# stm32.net
KiCad netlist of a schematic drawn in Altium Designer
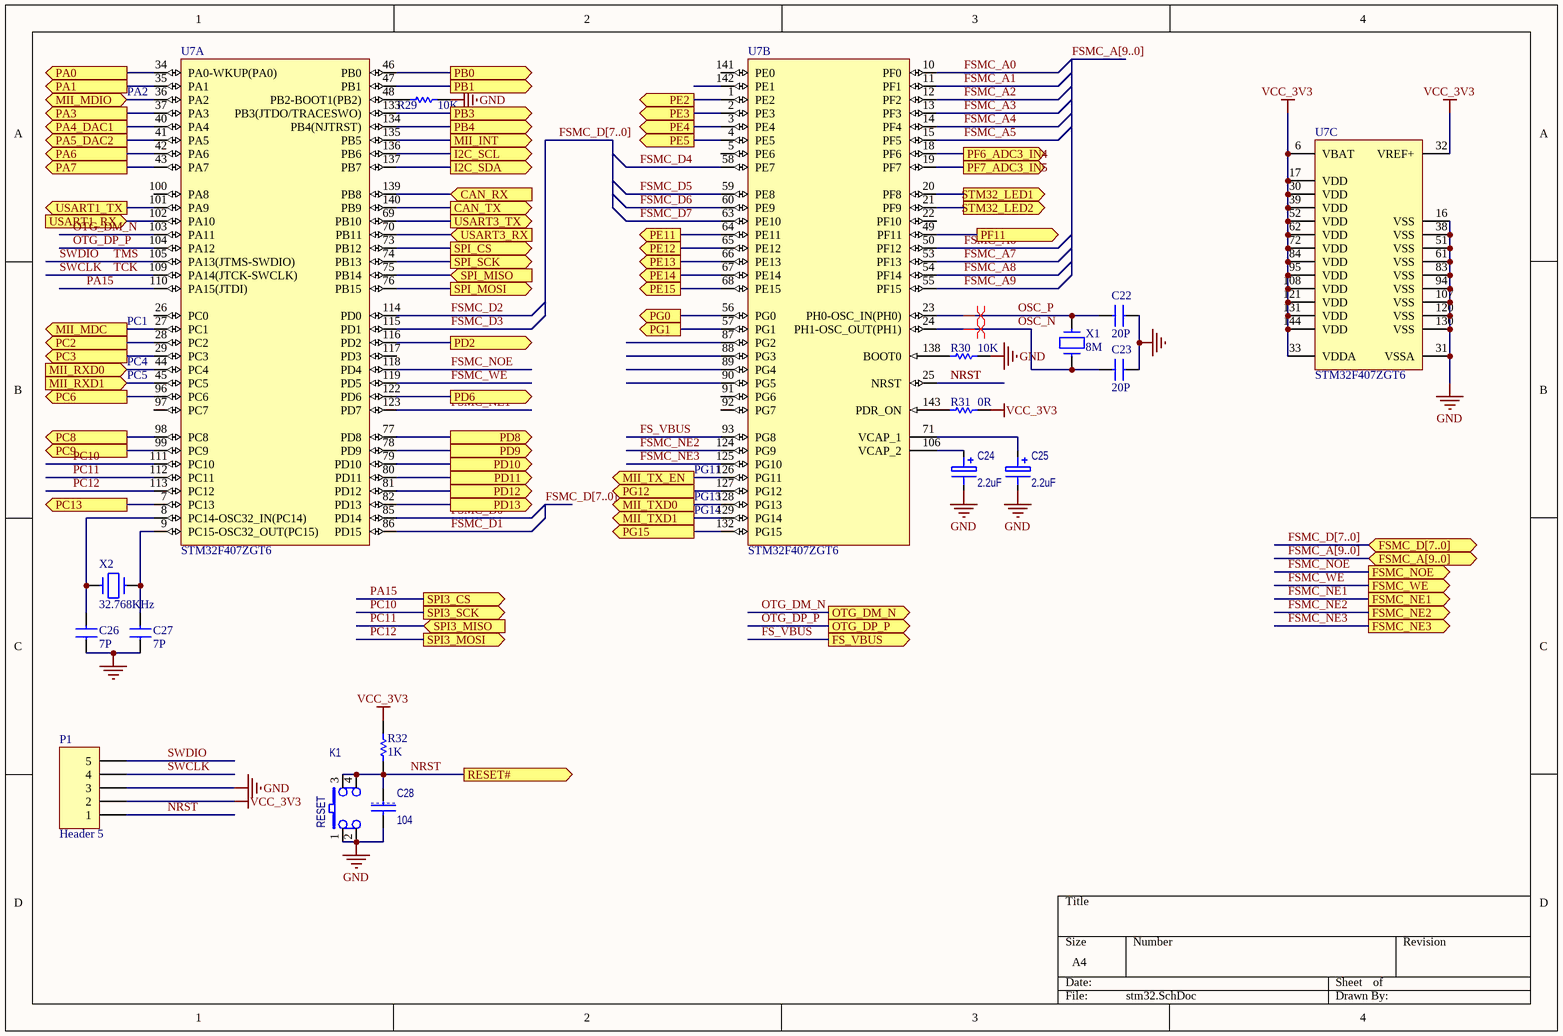
[diagram p0: stm32.SchDoc]

(export (version "E")
  (design (tool "Eeschema 10.0.6"))
  (components
    (comp (ref "C22")
      (value "20P")
      (footprint "0603C")
      (description "Capacitor")
      (libsource (lib "*") (part "CAP"))
    )
    (comp (ref "C23")
      (value "20P")
      (footprint "0603C")
      (description "Capacitor")
      (libsource (lib "*") (part "CAP"))
    )
    (comp (ref "C24") (value "2.2uF") (footprint "3216") (libsource (lib "*") (part "ELECTRO")))
    (comp (ref "C25") (value "2.2uF") (footprint "3216") (libsource (lib "*") (part "ELECTRO")))
    (comp (ref "C26")
      (value "7P")
      (footprint "0603C")
      (description "Capacitor")
      (libsource (lib "*") (part "CAP"))
    )
    (comp (ref "C27")
      (value "7P")
      (footprint "0603C")
      (description "Capacitor")
      (libsource (lib "*") (part "CAP"))
    )
    (comp (ref "C28")
      (value "104")
      (footprint "0603C")
      (description "Capacitor")
      (libsource (lib "") (part "CAP_1"))
    )
    (comp (ref "K1") (value "RESET") (footprint "SW_PIN4") (libsource (lib "*") (part "SW_PUSH2")))
    (comp (ref "P1")
      (value "Header 5")
      (footprint "HDR1X5")
      (description "Header, 5-Pin")
      (fields (field (name "PUBLISHER") "Altium Limited"))
      (libsource (lib "Miscellaneous Connectors") (part "Header 5"))
    )
    (comp (ref "R29")
      (value "10K")
      (footprint "0603R")
      (description "Semiconductor Resistor")
      (fields (field (name "PUBLISHER") "Altium Limited"))
      (libsource (lib "Miscellaneous Devices") (part "Res Semi"))
    )
    (comp (ref "R30")
      (value "10K")
      (footprint "0603R")
      (description "Semiconductor Resistor")
      (fields (field (name "PUBLISHER") "Altium Limited"))
      (libsource (lib "Miscellaneous Devices") (part "Res Semi"))
    )
    (comp (ref "R31")
      (value "0R")
      (footprint "0603R")
      (description "Semiconductor Resistor")
      (fields (field (name "Comment") "10K") (field (name "PUBLISHER") "Altium Limited"))
      (libsource (lib "Miscellaneous Devices") (part "Res Semi"))
    )
    (comp (ref "R32")
      (value "1K")
      (footprint "0603R")
      (description "Semiconductor Resistor")
      (fields (field (name "PUBLISHER") "Altium Limited"))
      (libsource (lib "Miscellaneous Devices") (part "Res Semi"))
    )
    (comp (ref "U7")
      (value "STM32F407ZGT6")
      (footprint "STM-LQFP144_N")
      (fields (field (name "MANUFACTURER") "STMicroelectronics"))
      (libsource (lib "STMicroelectronics STM32 F4") (part "STM32F407ZGT6"))
    )
    (comp (ref "X1") (value "8M") (footprint "XTAL3") (libsource (lib "*") (part "CRYSTAL")))
    (comp (ref "X2") (value "32.768KHz") (footprint "XTAL2") (libsource (lib "*") (part "CRYSTAL")))
  )
  (nets
    (net (code "1") (name "/CAN_RX") (class "Default")
      (node (ref "U7") (pin "139") (pinfunction "PB8_139") (pintype "bidirectional"))
    )
    (net (code "2") (name "/CAN_TX") (class "Default")
      (node (ref "U7") (pin "140") (pinfunction "PB9_140") (pintype "bidirectional"))
    )
    (net (code "3") (name "/FSMC_A0") (class "Default")
      (node (ref "U7") (pin "10") (pinfunction "PF0_10") (pintype "bidirectional"))
    )
    (net (code "4") (name "/FSMC_A1") (class "Default")
      (node (ref "U7") (pin "11") (pinfunction "PF1_11") (pintype "bidirectional"))
    )
    (net (code "5") (name "/FSMC_A2") (class "Default")
      (node (ref "U7") (pin "12") (pinfunction "PF2_12") (pintype "bidirectional"))
    )
    (net (code "6") (name "/FSMC_A3") (class "Default")
      (node (ref "U7") (pin "13") (pinfunction "PF3_13") (pintype "bidirectional"))
    )
    (net (code "7") (name "/FSMC_A4") (class "Default")
      (node (ref "U7") (pin "14") (pinfunction "PF4_14") (pintype "bidirectional"))
    )
    (net (code "8") (name "/FSMC_A5") (class "Default")
      (node (ref "U7") (pin "15") (pinfunction "PF5_15") (pintype "bidirectional"))
    )
    (net (code "9") (name "/FSMC_A6") (class "Default")
      (node (ref "U7") (pin "50") (pinfunction "PF12_50") (pintype "bidirectional"))
    )
    (net (code "10") (name "/FSMC_A7") (class "Default")
      (node (ref "U7") (pin "53") (pinfunction "PF13_53") (pintype "bidirectional"))
    )
    (net (code "11") (name "/FSMC_A8") (class "Default")
      (node (ref "U7") (pin "54") (pinfunction "PF14_54") (pintype "bidirectional"))
    )
    (net (code "12") (name "/FSMC_A9") (class "Default")
      (node (ref "U7") (pin "55") (pinfunction "PF15_55") (pintype "bidirectional"))
    )
    (net (code "14") (name "/FSMC_D0") (class "Default")
      (node (ref "U7") (pin "85") (pinfunction "PD14_85") (pintype "bidirectional"))
    )
    (net (code "15") (name "/FSMC_D1") (class "Default")
      (node (ref "U7") (pin "86") (pinfunction "PD15_86") (pintype "bidirectional"))
    )
    (net (code "16") (name "/FSMC_D2") (class "Default")
      (node (ref "U7") (pin "114") (pinfunction "PD0_114") (pintype "bidirectional"))
    )
    (net (code "17") (name "/FSMC_D3") (class "Default")
      (node (ref "U7") (pin "115") (pinfunction "PD1_115") (pintype "bidirectional"))
    )
    (net (code "18") (name "/FSMC_D4") (class "Default")
      (node (ref "U7") (pin "58") (pinfunction "PE7_58") (pintype "bidirectional"))
    )
    (net (code "19") (name "/FSMC_D5") (class "Default")
      (node (ref "U7") (pin "59") (pinfunction "PE8_59") (pintype "bidirectional"))
    )
    (net (code "20") (name "/FSMC_D6") (class "Default")
      (node (ref "U7") (pin "60") (pinfunction "PE9_60") (pintype "bidirectional"))
    )
    (net (code "21") (name "/FSMC_D7") (class "Default")
      (node (ref "U7") (pin "63") (pinfunction "PE10_63") (pintype "bidirectional"))
    )
    (net (code "23") (name "/FSMC_NE1") (class "Default")
      (node (ref "U7") (pin "123") (pinfunction "PD7_123") (pintype "bidirectional"))
    )
    (net (code "24") (name "/FSMC_NE2") (class "Default")
      (node (ref "U7") (pin "124") (pinfunction "PG9_124") (pintype "bidirectional"))
    )
    (net (code "25") (name "/FSMC_NE3") (class "Default")
      (node (ref "U7") (pin "125") (pinfunction "PG10_125") (pintype "bidirectional"))
    )
    (net (code "26") (name "/FSMC_NOE") (class "Default")
      (node (ref "U7") (pin "118") (pinfunction "PD4_118") (pintype "bidirectional"))
    )
    (net (code "27") (name "/FSMC_WE") (class "Default")
      (node (ref "U7") (pin "119") (pinfunction "PD5_119") (pintype "bidirectional"))
    )
    (net (code "28") (name "/FS_VBUS") (class "Default")
      (node (ref "U7") (pin "93") (pinfunction "PG8_93") (pintype "bidirectional"))
    )
    (net (code "29") (name "/I2C_SCL") (class "Default")
      (node (ref "U7") (pin "136") (pinfunction "PB6_136") (pintype "bidirectional"))
    )
    (net (code "30") (name "/I2C_SDA") (class "Default")
      (node (ref "U7") (pin "137") (pinfunction "PB7_137") (pintype "bidirectional"))
    )
    (net (code "31") (name "/MII_INT") (class "Default")
      (node (ref "U7") (pin "135") (pinfunction "PB5_135") (pintype "bidirectional"))
    )
    (net (code "32") (name "/MII_MDC") (class "Default")
      (node (ref "U7") (pin "27") (pinfunction "PC1_27") (pintype "bidirectional"))
    )
    (net (code "33") (name "/MII_MDIO") (class "Default")
      (node (ref "U7") (pin "36") (pinfunction "PA2_36") (pintype "bidirectional"))
    )
    (net (code "34") (name "/MII_RXD0") (class "Default")
      (node (ref "U7") (pin "44") (pinfunction "PC4_44") (pintype "bidirectional"))
    )
    (net (code "35") (name "/MII_RXD1") (class "Default")
      (node (ref "U7") (pin "45") (pinfunction "PC5_45") (pintype "bidirectional"))
    )
    (net (code "36") (name "/MII_TXD0") (class "Default")
      (node (ref "U7") (pin "128") (pinfunction "PG13_128") (pintype "bidirectional"))
    )
    (net (code "37") (name "/MII_TXD1") (class "Default")
      (node (ref "U7") (pin "129") (pinfunction "PG14_129") (pintype "bidirectional"))
    )
    (net (code "38") (name "/MII_TX_EN") (class "Default")
      (node (ref "U7") (pin "126") (pinfunction "PG11_126") (pintype "bidirectional"))
    )
    (net (code "39") (name "/NRST") (class "Default")
      (node (ref "C28") (pin "1") (pinfunction "1_1") (pintype "passive"))
      (node (ref "K1") (pin "3") (pinfunction "3_3") (pintype "passive"))
      (node (ref "K1") (pin "4") (pinfunction "4_4") (pintype "passive"))
      (node (ref "P1") (pin "1") (pinfunction "1_1") (pintype "passive"))
      (node (ref "R32") (pin "1") (pinfunction "1_1") (pintype "passive"))
      (node (ref "U7") (pin "25") (pinfunction "NRST_25") (pintype "bidirectional"))
    )
    (net (code "40") (name "/OSC_N") (class "Default")
      (node (ref "C23") (pin "2") (pinfunction "2_2") (pintype "passive"))
      (node (ref "U7") (pin "24") (pinfunction "PH1-OSC_OUT(PH1)_24") (pintype "bidirectional"))
      (node (ref "X1") (pin "2") (pintype "passive"))
    )
    (net (code "41") (name "/OSC_P") (class "Default")
      (node (ref "C22") (pin "2") (pinfunction "2_2") (pintype "passive"))
      (node (ref "U7") (pin "23") (pinfunction "PH0-OSC_IN(PH0)_23") (pintype "bidirectional"))
      (node (ref "X1") (pin "1") (pintype "passive"))
    )
    (net (code "42") (name "/OTG_DM_N") (class "Default")
      (node (ref "U7") (pin "103") (pinfunction "PA11_103") (pintype "bidirectional"))
    )
    (net (code "43") (name "/OTG_DP_P") (class "Default")
      (node (ref "U7") (pin "104") (pinfunction "PA12_104") (pintype "bidirectional"))
    )
    (net (code "44") (name "/PA0") (class "Default")
      (node (ref "U7") (pin "34") (pinfunction "PA0-WKUP(PA0)_34") (pintype "bidirectional"))
    )
    (net (code "45") (name "/PA1") (class "Default")
      (node (ref "U7") (pin "35") (pinfunction "PA1_35") (pintype "bidirectional"))
    )
    (net (code "46") (name "/PA3") (class "Default")
      (node (ref "U7") (pin "37") (pinfunction "PA3_37") (pintype "bidirectional"))
    )
    (net (code "47") (name "/PA4_DAC1") (class "Default")
      (node (ref "U7") (pin "40") (pinfunction "PA4_40") (pintype "bidirectional"))
    )
    (net (code "48") (name "/PA5_DAC2") (class "Default")
      (node (ref "U7") (pin "41") (pinfunction "PA5_41") (pintype "bidirectional"))
    )
    (net (code "49") (name "/PA6") (class "Default")
      (node (ref "U7") (pin "42") (pinfunction "PA6_42") (pintype "bidirectional"))
    )
    (net (code "50") (name "/PA7") (class "Default")
      (node (ref "U7") (pin "43") (pinfunction "PA7_43") (pintype "bidirectional"))
    )
    (net (code "51") (name "/PA15") (class "Default")
      (node (ref "U7") (pin "110") (pinfunction "PA15(JTDI)_110") (pintype "bidirectional"))
    )
    (net (code "52") (name "/PB0") (class "Default")
      (node (ref "U7") (pin "46") (pinfunction "PB0_46") (pintype "bidirectional"))
    )
    (net (code "53") (name "/PB1") (class "Default")
      (node (ref "U7") (pin "47") (pinfunction "PB1_47") (pintype "bidirectional"))
    )
    (net (code "54") (name "/PB3") (class "Default")
      (node (ref "U7") (pin "133") (pinfunction "PB3(JTDO/TRACESWO)_133") (pintype "bidirectional"))
    )
    (net (code "55") (name "/PB4") (class "Default")
      (node (ref "U7") (pin "134") (pinfunction "PB4(NJTRST)_134") (pintype "bidirectional"))
    )
    (net (code "56") (name "/PC2") (class "Default")
      (node (ref "U7") (pin "28") (pinfunction "PC2_28") (pintype "bidirectional"))
    )
    (net (code "57") (name "/PC3") (class "Default")
      (node (ref "U7") (pin "29") (pinfunction "PC3_29") (pintype "bidirectional"))
    )
    (net (code "58") (name "/PC6") (class "Default")
      (node (ref "U7") (pin "96") (pinfunction "PC6_96") (pintype "bidirectional"))
    )
    (net (code "59") (name "/PC8") (class "Default")
      (node (ref "U7") (pin "98") (pinfunction "PC8_98") (pintype "bidirectional"))
    )
    (net (code "60") (name "/PC9") (class "Default")
      (node (ref "U7") (pin "99") (pinfunction "PC9_99") (pintype "bidirectional"))
    )
    (net (code "61") (name "/PC10") (class "Default")
      (node (ref "U7") (pin "111") (pinfunction "PC10_111") (pintype "bidirectional"))
    )
    (net (code "62") (name "/PC11") (class "Default")
      (node (ref "U7") (pin "112") (pinfunction "PC11_112") (pintype "bidirectional"))
    )
    (net (code "63") (name "/PC12") (class "Default")
      (node (ref "U7") (pin "113") (pinfunction "PC12_113") (pintype "bidirectional"))
    )
    (net (code "64") (name "/PC13") (class "Default")
      (node (ref "U7") (pin "7") (pinfunction "PC13_7") (pintype "bidirectional"))
    )
    (net (code "65") (name "/PD2") (class "Default")
      (node (ref "U7") (pin "116") (pinfunction "PD2_116") (pintype "bidirectional"))
    )
    (net (code "66") (name "/PD6") (class "Default")
      (node (ref "U7") (pin "122") (pinfunction "PD6_122") (pintype "bidirectional"))
    )
    (net (code "67") (name "/PD8") (class "Default")
      (node (ref "U7") (pin "77") (pinfunction "PD8_77") (pintype "bidirectional"))
    )
    (net (code "68") (name "/PD9") (class "Default")
      (node (ref "U7") (pin "78") (pinfunction "PD9_78") (pintype "bidirectional"))
    )
    (net (code "69") (name "/PD10") (class "Default")
      (node (ref "U7") (pin "79") (pinfunction "PD10_79") (pintype "bidirectional"))
    )
    (net (code "70") (name "/PD11") (class "Default")
      (node (ref "U7") (pin "80") (pinfunction "PD11_80") (pintype "bidirectional"))
    )
    (net (code "71") (name "/PD12") (class "Default")
      (node (ref "U7") (pin "81") (pinfunction "PD12_81") (pintype "bidirectional"))
    )
    (net (code "72") (name "/PD13") (class "Default")
      (node (ref "U7") (pin "82") (pinfunction "PD13_82") (pintype "bidirectional"))
    )
    (net (code "73") (name "/PE2") (class "Default")
      (node (ref "U7") (pin "1") (pinfunction "PE2_1") (pintype "bidirectional"))
    )
    (net (code "74") (name "/PE3") (class "Default")
      (node (ref "U7") (pin "2") (pinfunction "PE3_2") (pintype "bidirectional"))
    )
    (net (code "75") (name "/PE4") (class "Default")
      (node (ref "U7") (pin "3") (pinfunction "PE4_3") (pintype "bidirectional"))
    )
    (net (code "76") (name "/PE5") (class "Default")
      (node (ref "U7") (pin "4") (pinfunction "PE5_4") (pintype "bidirectional"))
    )
    (net (code "77") (name "/PE11") (class "Default")
      (node (ref "U7") (pin "64") (pinfunction "PE11_64") (pintype "bidirectional"))
    )
    (net (code "78") (name "/PE12") (class "Default")
      (node (ref "U7") (pin "65") (pinfunction "PE12_65") (pintype "bidirectional"))
    )
    (net (code "79") (name "/PE13") (class "Default")
      (node (ref "U7") (pin "66") (pinfunction "PE13_66") (pintype "bidirectional"))
    )
    (net (code "80") (name "/PE14") (class "Default")
      (node (ref "U7") (pin "67") (pinfunction "PE14_67") (pintype "bidirectional"))
    )
    (net (code "81") (name "/PE15") (class "Default")
      (node (ref "U7") (pin "68") (pinfunction "PE15_68") (pintype "bidirectional"))
    )
    (net (code "82") (name "/PF6_ADC3_IN4") (class "Default")
      (node (ref "U7") (pin "18") (pinfunction "PF6_18") (pintype "bidirectional"))
    )
    (net (code "83") (name "/PF7_ADC3_IN5") (class "Default")
      (node (ref "U7") (pin "19") (pinfunction "PF7_19") (pintype "bidirectional"))
    )
    (net (code "84") (name "/PF11") (class "Default")
      (node (ref "U7") (pin "49") (pinfunction "PF11_49") (pintype "bidirectional"))
    )
    (net (code "85") (name "/PG0") (class "Default")
      (node (ref "U7") (pin "56") (pinfunction "PG0_56") (pintype "bidirectional"))
    )
    (net (code "86") (name "/PG1") (class "Default")
      (node (ref "U7") (pin "57") (pinfunction "PG1_57") (pintype "bidirectional"))
    )
    (net (code "87") (name "/PG12") (class "Default")
      (node (ref "U7") (pin "127") (pinfunction "PG12_127") (pintype "bidirectional"))
    )
    (net (code "88") (name "/PG15") (class "Default")
      (node (ref "U7") (pin "132") (pinfunction "PG15_132") (pintype "bidirectional"))
    )
    (net (code "89") (name "/SPI_CS") (class "Default")
      (node (ref "U7") (pin "73") (pinfunction "PB12_73") (pintype "bidirectional"))
    )
    (net (code "90") (name "/SPI_MISO") (class "Default")
      (node (ref "U7") (pin "75") (pinfunction "PB14_75") (pintype "bidirectional"))
    )
    (net (code "91") (name "/SPI_MOSI") (class "Default")
      (node (ref "U7") (pin "76") (pinfunction "PB15_76") (pintype "bidirectional"))
    )
    (net (code "92") (name "/SPI_SCK") (class "Default")
      (node (ref "U7") (pin "74") (pinfunction "PB13_74") (pintype "bidirectional"))
    )
    (net (code "93") (name "/STM32_LED1") (class "Default")
      (node (ref "U7") (pin "20") (pinfunction "PF8_20") (pintype "bidirectional"))
    )
    (net (code "94") (name "/STM32_LED2") (class "Default")
      (node (ref "U7") (pin "21") (pinfunction "PF9_21") (pintype "bidirectional"))
    )
    (net (code "95") (name "/SWCLK") (class "Default")
      (node (ref "P1") (pin "4") (pinfunction "4_4") (pintype "passive"))
      (node (ref "U7") (pin "109") (pinfunction "PA14(JTCK-SWCLK)_109") (pintype "bidirectional"))
    )
    (net (code "96") (name "/SWDIO") (class "Default")
      (node (ref "P1") (pin "5") (pinfunction "5_5") (pintype "passive"))
      (node (ref "U7") (pin "105") (pinfunction "PA13(JTMS-SWDIO)_105") (pintype "bidirectional"))
    )
    (net (code "97") (name "/USART1_RX") (class "Default")
      (node (ref "U7") (pin "102") (pinfunction "PA10_102") (pintype "bidirectional"))
    )
    (net (code "98") (name "/USART1_TX") (class "Default")
      (node (ref "U7") (pin "101") (pinfunction "PA9_101") (pintype "bidirectional"))
    )
    (net (code "99") (name "/USART3_RX") (class "Default")
      (node (ref "U7") (pin "70") (pinfunction "PB11_70") (pintype "bidirectional"))
    )
    (net (code "100") (name "/USART3_TX") (class "Default")
      (node (ref "U7") (pin "69") (pinfunction "PB10_69") (pintype "bidirectional"))
    )
    (net (code "101") (name "GND") (class "Default")
      (node (ref "C22") (pin "1") (pinfunction "1_1") (pintype "passive"))
      (node (ref "C23") (pin "1") (pinfunction "1_1") (pintype "passive"))
      (node (ref "C24") (pin "2") (pinfunction "2_2") (pintype "passive"))
      (node (ref "C25") (pin "2") (pinfunction "2_2") (pintype "passive"))
      (node (ref "C26") (pin "1") (pinfunction "1_1") (pintype "passive"))
      (node (ref "C27") (pin "1") (pinfunction "1_1") (pintype "passive"))
      (node (ref "C28") (pin "2") (pinfunction "2_2") (pintype "passive"))
      (node (ref "K1") (pin "1") (pinfunction "1_1") (pintype "passive"))
      (node (ref "K1") (pin "2") (pinfunction "2_2") (pintype "passive"))
      (node (ref "P1") (pin "3") (pinfunction "3_3") (pintype "passive"))
      (node (ref "R29") (pin "1") (pinfunction "1_1") (pintype "passive"))
      (node (ref "R30") (pin "2") (pinfunction "2_2") (pintype "passive"))
      (node (ref "U7") (pin "107") (pinfunction "VSS_107") (pintype "power_in"))
      (node (ref "U7") (pin "120") (pinfunction "VSS_120") (pintype "power_in"))
      (node (ref "U7") (pin "130") (pinfunction "VSS_130") (pintype "power_in"))
      (node (ref "U7") (pin "16") (pinfunction "VSS_16") (pintype "power_in"))
      (node (ref "U7") (pin "31") (pinfunction "VSSA_31") (pintype "power_in"))
      (node (ref "U7") (pin "38") (pinfunction "VSS_38") (pintype "power_in"))
      (node (ref "U7") (pin "51") (pinfunction "VSS_51") (pintype "power_in"))
      (node (ref "U7") (pin "61") (pinfunction "VSS_61") (pintype "power_in"))
      (node (ref "U7") (pin "83") (pinfunction "VSS_83") (pintype "power_in"))
      (node (ref "U7") (pin "94") (pinfunction "VSS_94") (pintype "power_in"))
    )
    (net (code "102") (name "Net-(U7A-PB2-BOOT1(PB2))") (class "Default")
      (node (ref "R29") (pin "2") (pinfunction "2_2") (pintype "passive"))
      (node (ref "U7") (pin "48") (pinfunction "PB2-BOOT1(PB2)_48") (pintype "bidirectional"))
    )
    (net (code "103") (name "Net-(U7A-PC14-OSC32_IN(PC14))") (class "Default")
      (node (ref "C26") (pin "2") (pinfunction "2_2") (pintype "passive"))
      (node (ref "U7") (pin "8") (pinfunction "PC14-OSC32_IN(PC14)_8") (pintype "bidirectional"))
      (node (ref "X2") (pin "2") (pintype "passive"))
    )
    (net (code "104") (name "Net-(U7A-PC15-OSC32_OUT(PC15))") (class "Default")
      (node (ref "C27") (pin "2") (pinfunction "2_2") (pintype "passive"))
      (node (ref "U7") (pin "9") (pinfunction "PC15-OSC32_OUT(PC15)_9") (pintype "bidirectional"))
      (node (ref "X2") (pin "1") (pintype "passive"))
    )
    (net (code "105") (name "Net-(U7B-BOOT0)") (class "Default")
      (node (ref "R30") (pin "1") (pinfunction "1_1") (pintype "passive"))
      (node (ref "U7") (pin "138") (pinfunction "BOOT0_138") (pintype "input"))
    )
    (net (code "106") (name "Net-(U7B-PDR_ON)") (class "Default")
      (node (ref "R31") (pin "1") (pinfunction "1_1") (pintype "passive"))
      (node (ref "U7") (pin "143") (pinfunction "PDR_ON_143") (pintype "input"))
    )
    (net (code "107") (name "Net-(U7B-VCAP_1)") (class "Default")
      (node (ref "C25") (pin "1") (pinfunction "1_1") (pintype "passive"))
      (node (ref "U7") (pin "71") (pinfunction "VCAP_1_71") (pintype "power_in"))
    )
    (net (code "108") (name "Net-(U7B-VCAP_2)") (class "Default")
      (node (ref "C24") (pin "1") (pinfunction "1_1") (pintype "passive"))
      (node (ref "U7") (pin "106") (pinfunction "VCAP_2_106") (pintype "power_in"))
    )
    (net (code "109") (name "VCC_3V3") (class "Default")
      (node (ref "P1") (pin "2") (pinfunction "2_2") (pintype "passive"))
      (node (ref "R31") (pin "2") (pinfunction "2_2") (pintype "passive"))
      (node (ref "R32") (pin "2") (pinfunction "2_2") (pintype "passive"))
      (node (ref "U7") (pin "108") (pinfunction "VDD_108") (pintype "power_in"))
      (node (ref "U7") (pin "121") (pinfunction "VDD_121") (pintype "power_in"))
      (node (ref "U7") (pin "131") (pinfunction "VDD_131") (pintype "power_in"))
      (node (ref "U7") (pin "144") (pinfunction "VDD_144") (pintype "power_in"))
      (node (ref "U7") (pin "17") (pinfunction "VDD_17") (pintype "power_in"))
      (node (ref "U7") (pin "30") (pinfunction "VDD_30") (pintype "power_in"))
      (node (ref "U7") (pin "32") (pinfunction "VREF+_32") (pintype "power_in"))
      (node (ref "U7") (pin "33") (pinfunction "VDDA_33") (pintype "power_in"))
      (node (ref "U7") (pin "39") (pinfunction "VDD_39") (pintype "power_in"))
      (node (ref "U7") (pin "52") (pinfunction "VDD_52") (pintype "power_in"))
      (node (ref "U7") (pin "6") (pinfunction "VBAT_6") (pintype "power_in"))
      (node (ref "U7") (pin "62") (pinfunction "VDD_62") (pintype "power_in"))
      (node (ref "U7") (pin "72") (pinfunction "VDD_72") (pintype "power_in"))
      (node (ref "U7") (pin "84") (pinfunction "VDD_84") (pintype "power_in"))
      (node (ref "U7") (pin "95") (pinfunction "VDD_95") (pintype "power_in"))
    )
    (net (code "110") (name "unconnected-(U7A-PA8-Pad100)") (class "Default")
      (node (ref "U7") (pin "100") (pinfunction "PA8_100") (pintype "bidirectional"))
    )
    (net (code "111") (name "unconnected-(U7A-PC0-Pad26)") (class "Default")
      (node (ref "U7") (pin "26") (pinfunction "PC0_26") (pintype "bidirectional"))
    )
    (net (code "112") (name "unconnected-(U7A-PC7-Pad97)") (class "Default")
      (node (ref "U7") (pin "97") (pinfunction "PC7_97") (pintype "bidirectional"))
    )
    (net (code "113") (name "unconnected-(U7A-PD3-Pad117)") (class "Default")
      (node (ref "U7") (pin "117") (pinfunction "PD3_117") (pintype "bidirectional"))
    )
    (net (code "114") (name "unconnected-(U7B-PE0-Pad141)") (class "Default")
      (node (ref "U7") (pin "141") (pinfunction "PE0_141") (pintype "bidirectional"))
    )
    (net (code "115") (name "unconnected-(U7B-PE1-Pad142)") (class "Default")
      (node (ref "U7") (pin "142") (pinfunction "PE1_142") (pintype "bidirectional"))
    )
    (net (code "116") (name "unconnected-(U7B-PE6-Pad5)") (class "Default")
      (node (ref "U7") (pin "5") (pinfunction "PE6_5") (pintype "bidirectional"))
    )
    (net (code "117") (name "unconnected-(U7B-PF10-Pad22)") (class "Default")
      (node (ref "U7") (pin "22") (pinfunction "PF10_22") (pintype "bidirectional"))
    )
    (net (code "118") (name "unconnected-(U7B-PG2-Pad87)") (class "Default")
      (node (ref "U7") (pin "87") (pinfunction "PG2_87") (pintype "bidirectional"))
    )
    (net (code "119") (name "unconnected-(U7B-PG3-Pad88)") (class "Default")
      (node (ref "U7") (pin "88") (pinfunction "PG3_88") (pintype "bidirectional"))
    )
    (net (code "120") (name "unconnected-(U7B-PG4-Pad89)") (class "Default")
      (node (ref "U7") (pin "89") (pinfunction "PG4_89") (pintype "bidirectional"))
    )
    (net (code "121") (name "unconnected-(U7B-PG5-Pad90)") (class "Default")
      (node (ref "U7") (pin "90") (pinfunction "PG5_90") (pintype "bidirectional"))
    )
    (net (code "122") (name "unconnected-(U7B-PG6-Pad91)") (class "Default")
      (node (ref "U7") (pin "91") (pinfunction "PG6_91") (pintype "bidirectional"))
    )
    (net (code "123") (name "unconnected-(U7B-PG7-Pad92)") (class "Default")
      (node (ref "U7") (pin "92") (pinfunction "PG7_92") (pintype "bidirectional"))
    )
  )
)
